# Banks_7_8.net
KiCad netlist of a schematic drawn in Altium Designer
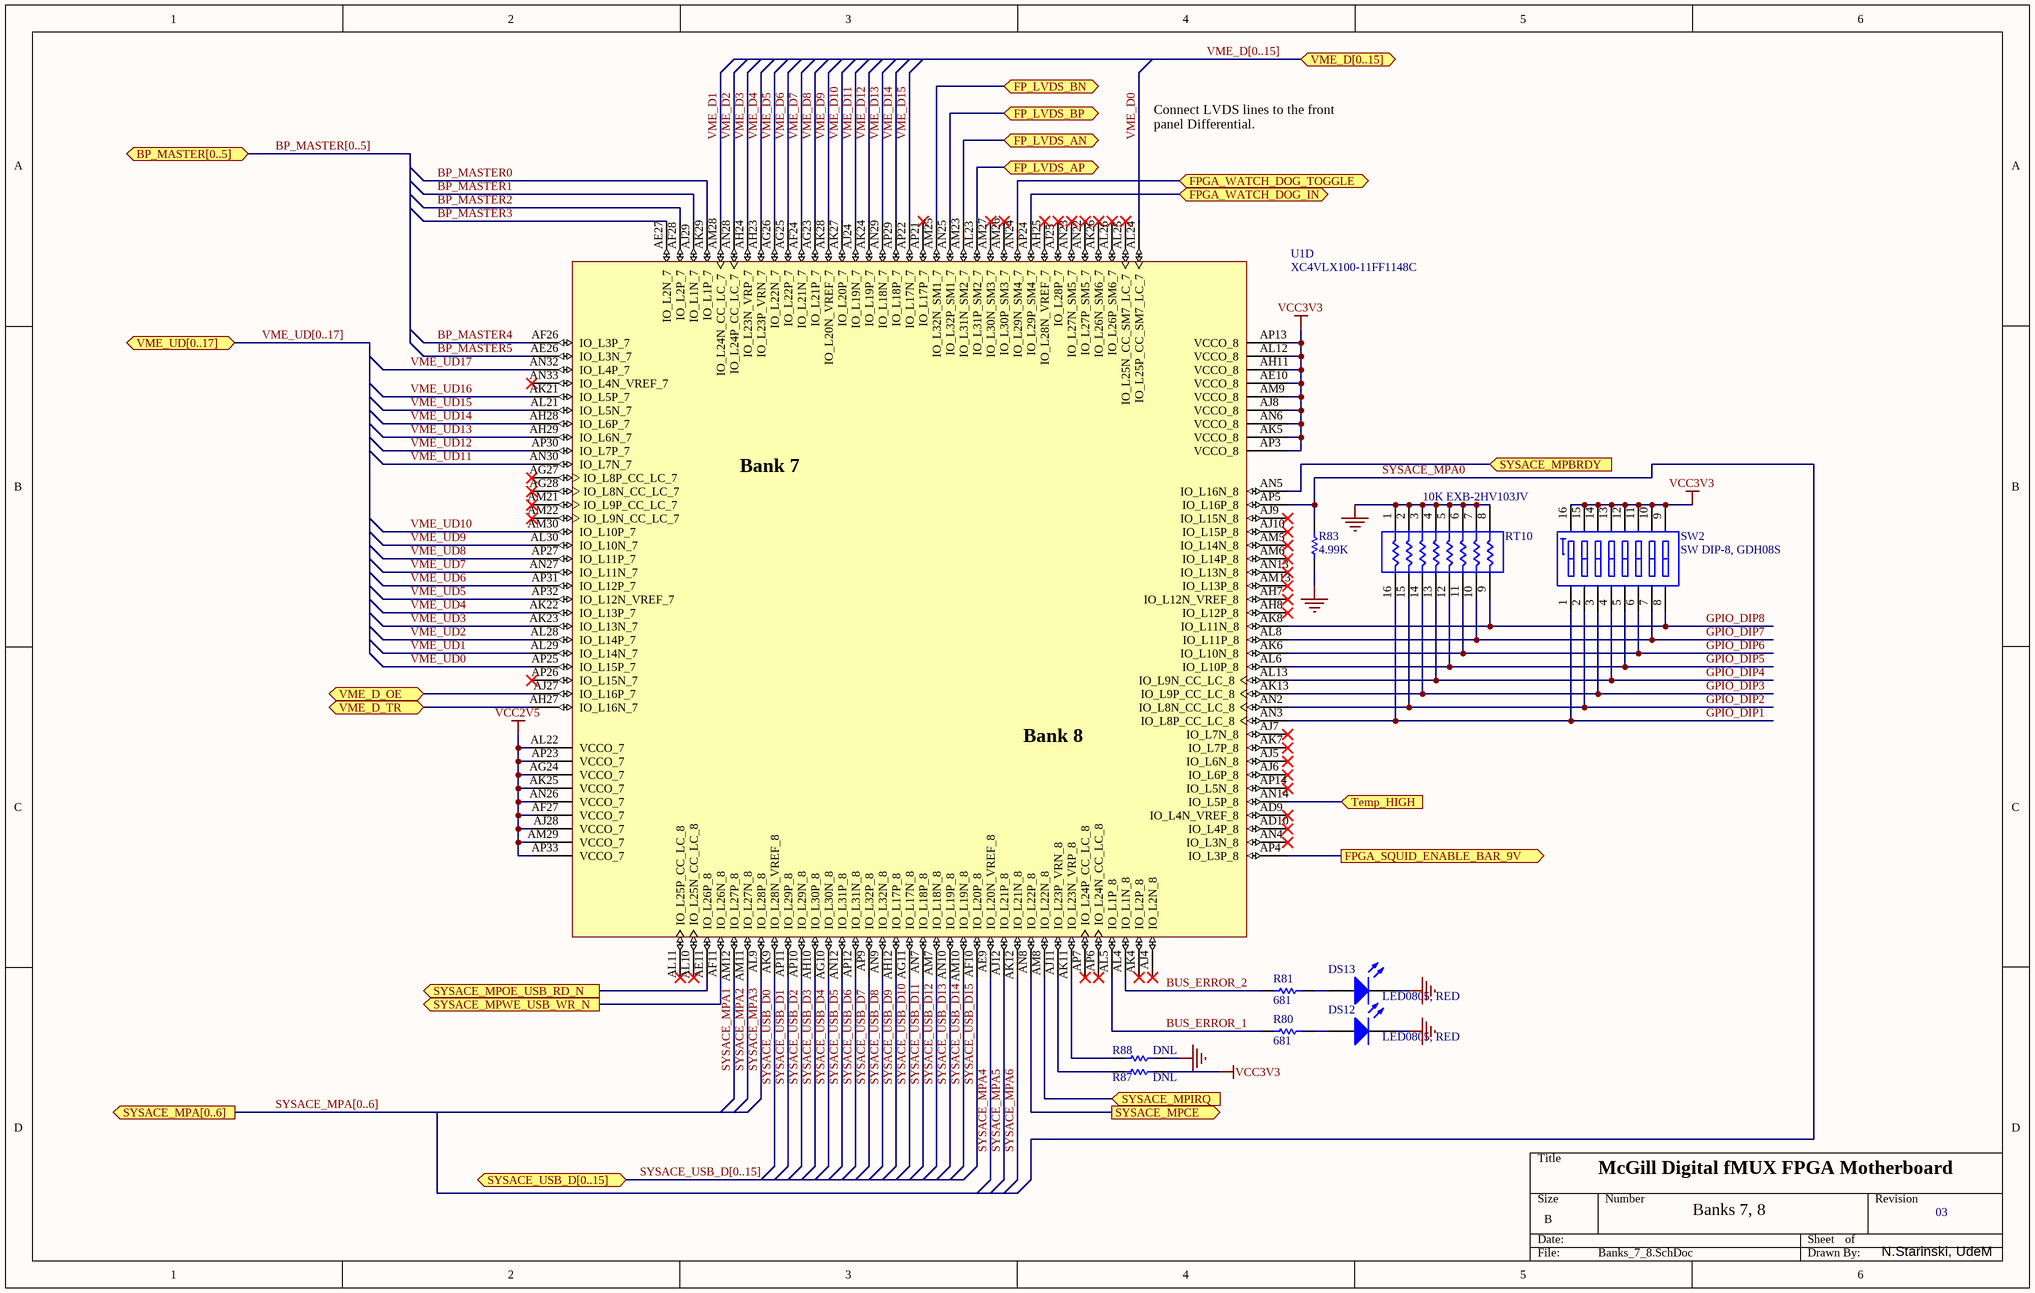
[diagram p0: Banks_7_8.SchDoc]

(export (version "E")
  (design (tool "Eeschema 10.0.6"))
  (components
    (comp (ref "DS12")
      (value "LED0805, RED")
      (footprint "SMD _LED")
      (description "LED 0805 LTST-C170CKT")
      (fields (field (name "PUBLISHER") "Altium Limited"))
      (libsource (lib "Miscellaneous Devices") (part "LED3"))
    )
    (comp (ref "DS13")
      (value "LED0805, RED")
      (footprint "SMD _LED")
      (description "LED 0805 LTST-C170CKT")
      (fields (field (name "PUBLISHER") "Altium Limited"))
      (libsource (lib "Miscellaneous Devices") (part "LED3"))
    )
    (comp (ref "R80")
      (value "681")
      (footprint "CR1608-0603")
      (description "Resistor 0603")
      (fields (field (name "PUBLISHER") "Altium Limited"))
      (libsource (lib "Miscellaneous Devices") (part "Res Semi"))
    )
    (comp (ref "R81")
      (value "681")
      (footprint "CR1608-0603")
      (description "Resistor 0603")
      (fields (field (name "PUBLISHER") "Altium Limited"))
      (libsource (lib "Miscellaneous Devices") (part "Res Semi"))
    )
    (comp (ref "R83")
      (value "4.99K")
      (footprint "CR1608-0603")
      (description "Resistor 0603")
      (fields (field (name "PUBLISHER") "Altium Limited"))
      (libsource (lib "Miscellaneous Devices") (part "Res Semi"))
    )
    (comp (ref "R87")
      (value "DNL")
      (footprint "CR1608-0603")
      (description "Semiconductor Resistor")
      (fields (field (name "PUBLISHER") "Altium Limited"))
      (libsource (lib "Miscellaneous Devices") (part "Res Semi"))
    )
    (comp (ref "R88")
      (value "DNL")
      (footprint "CR1608-0603")
      (description "Semiconductor Resistor")
      (fields (field (name "PUBLISHER") "Altium Limited"))
      (libsource (lib "Miscellaneous Devices") (part "Res Semi"))
    )
    (comp (ref "RT10")
      (value "10K EXB-2HV103JV")
      (footprint "0402_Array_2HV")
      (description "Isolated Resistor Network")
      (fields (field (name "PUBLISHER") "Altium Limited"))
      (libsource (lib "Miscellaneous Devices 02") (part "Res Pack3"))
    )
    (comp (ref "SW2")
      (value "SW DIP-8, GDH08S")
      (footprint "DIP_SW_8WAY_SMD")
      (description "DIP Switch, 8 Position, SPST")
      (fields (field (name "PUBLISHER") "Altium Limited"))
      (libsource (lib "Miscellaneous Devices 02") (part "SW DIP-8"))
    )
    (comp (ref "U1")
      (value "XC4VLX100-11FF1148C")
      (footprint "FF1148")
      (description "Xilinx Virtex-4 LX Platform FPGA, 1148-Ball FFBGA, Speed Grade 11, 768 User I/Os, Commercial Grade")
      (fields (field (name "PUBLISHER") "Altium Limited"))
      (libsource (lib "Xilinx Virtex-4") (part "XC4VLX100-11FF1148C"))
    )
  )
  (nets
    (net (code "1") (name "/BP_MASTER0") (class "Default")
      (node (ref "U1") (pin "AK29") (pinfunction "IO_L1P_7_AK29") (pintype "bidirectional"))
    )
    (net (code "2") (name "/BP_MASTER1") (class "Default")
      (node (ref "U1") (pin "AJ29") (pinfunction "IO_L1N_7_AJ29") (pintype "bidirectional"))
    )
    (net (code "3") (name "/BP_MASTER2") (class "Default")
      (node (ref "U1") (pin "AF28") (pinfunction "IO_L2P_7_AF28") (pintype "bidirectional"))
    )
    (net (code "4") (name "/BP_MASTER3") (class "Default")
      (node (ref "U1") (pin "AE27") (pinfunction "IO_L2N_7_AE27") (pintype "bidirectional"))
    )
    (net (code "5") (name "/BP_MASTER4") (class "Default")
      (node (ref "U1") (pin "AF26") (pinfunction "IO_L3P_7_AF26") (pintype "bidirectional"))
    )
    (net (code "6") (name "/BP_MASTER5") (class "Default")
      (node (ref "U1") (pin "AE26") (pinfunction "IO_L3N_7_AE26") (pintype "bidirectional"))
    )
    (net (code "8") (name "/BUS_ERROR_1") (class "Default")
      (node (ref "R80") (pin "1") (pinfunction "1_1") (pintype "passive"))
      (node (ref "U1") (pin "AL5") (pinfunction "IO_L1P_8_AL5") (pintype "bidirectional"))
    )
    (net (code "9") (name "/BUS_ERROR_2") (class "Default")
      (node (ref "R81") (pin "1") (pinfunction "1_1") (pintype "passive"))
      (node (ref "U1") (pin "AL4") (pinfunction "IO_L1N_8_AL4") (pintype "bidirectional"))
    )
    (net (code "10") (name "/FPGA_SQUID_ENABLE_BAR_9V") (class "Default")
      (node (ref "U1") (pin "AP4") (pinfunction "IO_L3P_8_AP4") (pintype "bidirectional"))
    )
    (net (code "11") (name "/FPGA_WATCH_DOG_IN") (class "Default")
      (node (ref "U1") (pin "AP24") (pinfunction "IO_L29P_SM4_7_AP24") (pintype "bidirectional"))
    )
    (net (code "12") (name "/FPGA_WATCH_DOG_TOGGLE") (class "Default")
      (node (ref "U1") (pin "AN24") (pinfunction "IO_L29N_SM4_7_AN24") (pintype "bidirectional"))
    )
    (net (code "13") (name "/FP_LVDS_AN") (class "Default")
      (node (ref "U1") (pin "AM23") (pinfunction "IO_L31N_SM2_7_AM23") (pintype "bidirectional"))
    )
    (net (code "14") (name "/FP_LVDS_AP") (class "Default")
      (node (ref "U1") (pin "AL23") (pinfunction "IO_L31P_SM2_7_AL23") (pintype "bidirectional"))
    )
    (net (code "15") (name "/FP_LVDS_BN") (class "Default")
      (node (ref "U1") (pin "AM25") (pinfunction "IO_L32N_SM1_7_AM25") (pintype "bidirectional"))
    )
    (net (code "16") (name "/FP_LVDS_BP") (class "Default")
      (node (ref "U1") (pin "AN25") (pinfunction "IO_L32P_SM1_7_AN25") (pintype "bidirectional"))
    )
    (net (code "17") (name "/GPIO_DIP1") (class "Default")
      (node (ref "RT10") (pin "16") (pinfunction "16_16") (pintype "passive"))
      (node (ref "SW2") (pin "1") (pinfunction "A1_1") (pintype "passive"))
      (node (ref "U1") (pin "AN3") (pinfunction "IO_L8P_CC_LC_8_AN3") (pintype "bidirectional"))
    )
    (net (code "18") (name "/GPIO_DIP2") (class "Default")
      (node (ref "RT10") (pin "15") (pinfunction "15_15") (pintype "passive"))
      (node (ref "SW2") (pin "2") (pinfunction "A2_2") (pintype "passive"))
      (node (ref "U1") (pin "AN2") (pinfunction "IO_L8N_CC_LC_8_AN2") (pintype "bidirectional"))
    )
    (net (code "19") (name "/GPIO_DIP3") (class "Default")
      (node (ref "RT10") (pin "14") (pinfunction "14_14") (pintype "passive"))
      (node (ref "SW2") (pin "3") (pinfunction "A3_3") (pintype "passive"))
      (node (ref "U1") (pin "AK13") (pinfunction "IO_L9P_CC_LC_8_AK13") (pintype "bidirectional"))
    )
    (net (code "20") (name "/GPIO_DIP4") (class "Default")
      (node (ref "RT10") (pin "13") (pinfunction "13_13") (pintype "passive"))
      (node (ref "SW2") (pin "4") (pinfunction "A4_4") (pintype "passive"))
      (node (ref "U1") (pin "AL13") (pinfunction "IO_L9N_CC_LC_8_AL13") (pintype "bidirectional"))
    )
    (net (code "21") (name "/GPIO_DIP5") (class "Default")
      (node (ref "RT10") (pin "12") (pinfunction "12_12") (pintype "passive"))
      (node (ref "SW2") (pin "5") (pinfunction "A5_5") (pintype "passive"))
      (node (ref "U1") (pin "AL6") (pinfunction "IO_L10P_8_AL6") (pintype "bidirectional"))
    )
    (net (code "22") (name "/GPIO_DIP6") (class "Default")
      (node (ref "RT10") (pin "11") (pinfunction "11_11") (pintype "passive"))
      (node (ref "SW2") (pin "6") (pinfunction "A6_6") (pintype "passive"))
      (node (ref "U1") (pin "AK6") (pinfunction "IO_L10N_8_AK6") (pintype "bidirectional"))
    )
    (net (code "23") (name "/GPIO_DIP7") (class "Default")
      (node (ref "RT10") (pin "10") (pinfunction "10_10") (pintype "passive"))
      (node (ref "SW2") (pin "7") (pinfunction "A7_7") (pintype "passive"))
      (node (ref "U1") (pin "AL8") (pinfunction "IO_L11P_8_AL8") (pintype "bidirectional"))
    )
    (net (code "24") (name "/GPIO_DIP8") (class "Default")
      (node (ref "RT10") (pin "9") (pinfunction "9_9") (pintype "passive"))
      (node (ref "SW2") (pin "8") (pinfunction "A8_8") (pintype "passive"))
      (node (ref "U1") (pin "AK8") (pinfunction "IO_L11N_8_AK8") (pintype "bidirectional"))
    )
    (net (code "25") (name "/SYSACE_MPA0") (class "Default")
      (node (ref "R83") (pin "2") (pinfunction "2_2") (pintype "passive"))
      (node (ref "U1") (pin "AP5") (pinfunction "IO_L16P_8_AP5") (pintype "bidirectional"))
    )
    (net (code "26") (name "/SYSACE_MPA1") (class "Default")
      (node (ref "U1") (pin "AM12") (pinfunction "IO_L27P_8_AM12") (pintype "bidirectional"))
    )
    (net (code "27") (name "/SYSACE_MPA2") (class "Default")
      (node (ref "U1") (pin "AM11") (pinfunction "IO_L27N_8_AM11") (pintype "bidirectional"))
    )
    (net (code "28") (name "/SYSACE_MPA3") (class "Default")
      (node (ref "U1") (pin "AL9") (pinfunction "IO_L28P_8_AL9") (pintype "bidirectional"))
    )
    (net (code "29") (name "/SYSACE_MPA4") (class "Default")
      (node (ref "U1") (pin "AE9") (pinfunction "IO_L20N_VREF_8_AE9") (pintype "bidirectional"))
    )
    (net (code "30") (name "/SYSACE_MPA5") (class "Default")
      (node (ref "U1") (pin "AJ12") (pinfunction "IO_L21P_8_AJ12") (pintype "bidirectional"))
    )
    (net (code "31") (name "/SYSACE_MPA6") (class "Default")
      (node (ref "U1") (pin "AK12") (pinfunction "IO_L21N_8_AK12") (pintype "bidirectional"))
    )
    (net (code "33") (name "/SYSACE_MPBRDY") (class "Default")
      (node (ref "U1") (pin "AN5") (pinfunction "IO_L16N_8_AN5") (pintype "bidirectional"))
    )
    (net (code "34") (name "/SYSACE_MPCE") (class "Default")
      (node (ref "U1") (pin "AN8") (pinfunction "IO_L22P_8_AN8") (pintype "bidirectional"))
    )
    (net (code "35") (name "/SYSACE_MPIRQ") (class "Default")
      (node (ref "U1") (pin "AM8") (pinfunction "IO_L22N_8_AM8") (pintype "bidirectional"))
    )
    (net (code "36") (name "/SYSACE_MPOE_USB_RD_N") (class "Default")
      (node (ref "U1") (pin "AE11") (pinfunction "IO_L26P_8_AE11") (pintype "bidirectional"))
    )
    (net (code "37") (name "/SYSACE_MPWE_USB_WR_N") (class "Default")
      (node (ref "U1") (pin "AF11") (pinfunction "IO_L26N_8_AF11") (pintype "bidirectional"))
    )
    (net (code "38") (name "/SYSACE_USB_D0") (class "Default")
      (node (ref "U1") (pin "AK9") (pinfunction "IO_L28N_VREF_8_AK9") (pintype "bidirectional"))
    )
    (net (code "39") (name "/SYSACE_USB_D1") (class "Default")
      (node (ref "U1") (pin "AP11") (pinfunction "IO_L29P_8_AP11") (pintype "bidirectional"))
    )
    (net (code "40") (name "/SYSACE_USB_D2") (class "Default")
      (node (ref "U1") (pin "AP10") (pinfunction "IO_L29N_8_AP10") (pintype "bidirectional"))
    )
    (net (code "41") (name "/SYSACE_USB_D3") (class "Default")
      (node (ref "U1") (pin "AH10") (pinfunction "IO_L30P_8_AH10") (pintype "bidirectional"))
    )
    (net (code "42") (name "/SYSACE_USB_D4") (class "Default")
      (node (ref "U1") (pin "AG10") (pinfunction "IO_L30N_8_AG10") (pintype "bidirectional"))
    )
    (net (code "43") (name "/SYSACE_USB_D5") (class "Default")
      (node (ref "U1") (pin "AN12") (pinfunction "IO_L31P_8_AN12") (pintype "bidirectional"))
    )
    (net (code "44") (name "/SYSACE_USB_D6") (class "Default")
      (node (ref "U1") (pin "AP12") (pinfunction "IO_L31N_8_AP12") (pintype "bidirectional"))
    )
    (net (code "45") (name "/SYSACE_USB_D7") (class "Default")
      (node (ref "U1") (pin "AP9") (pinfunction "IO_L32P_8_AP9") (pintype "bidirectional"))
    )
    (net (code "46") (name "/SYSACE_USB_D8") (class "Default")
      (node (ref "U1") (pin "AN9") (pinfunction "IO_L32N_8_AN9") (pintype "bidirectional"))
    )
    (net (code "47") (name "/SYSACE_USB_D9") (class "Default")
      (node (ref "U1") (pin "AH12") (pinfunction "IO_L17P_8_AH12") (pintype "bidirectional"))
    )
    (net (code "48") (name "/SYSACE_USB_D10") (class "Default")
      (node (ref "U1") (pin "AG11") (pinfunction "IO_L17N_8_AG11") (pintype "bidirectional"))
    )
    (net (code "49") (name "/SYSACE_USB_D11") (class "Default")
      (node (ref "U1") (pin "AN7") (pinfunction "IO_L18P_8_AN7") (pintype "bidirectional"))
    )
    (net (code "50") (name "/SYSACE_USB_D12") (class "Default")
      (node (ref "U1") (pin "AM7") (pinfunction "IO_L18N_8_AM7") (pintype "bidirectional"))
    )
    (net (code "51") (name "/SYSACE_USB_D13") (class "Default")
      (node (ref "U1") (pin "AN10") (pinfunction "IO_L19P_8_AN10") (pintype "bidirectional"))
    )
    (net (code "52") (name "/SYSACE_USB_D14") (class "Default")
      (node (ref "U1") (pin "AM10") (pinfunction "IO_L19N_8_AM10") (pintype "bidirectional"))
    )
    (net (code "53") (name "/SYSACE_USB_D15") (class "Default")
      (node (ref "U1") (pin "AF10") (pinfunction "IO_L20P_8_AF10") (pintype "bidirectional"))
    )
    (net (code "55") (name "/Temp_HIGH") (class "Default")
      (node (ref "U1") (pin "AN14") (pinfunction "IO_L5P_8_AN14") (pintype "bidirectional"))
    )
    (net (code "56") (name "/VME_D0") (class "Default")
      (node (ref "U1") (pin "AL24") (pinfunction "IO_L25P_CC_SM7_LC_7_AL24") (pintype "bidirectional"))
    )
    (net (code "57") (name "/VME_D1") (class "Default")
      (node (ref "U1") (pin "AM28") (pinfunction "IO_L24N_CC_LC_7_AM28") (pintype "bidirectional"))
    )
    (net (code "58") (name "/VME_D2") (class "Default")
      (node (ref "U1") (pin "AN28") (pinfunction "IO_L24P_CC_LC_7_AN28") (pintype "bidirectional"))
    )
    (net (code "59") (name "/VME_D3") (class "Default")
      (node (ref "U1") (pin "AH24") (pinfunction "IO_L23N_VRP_7_AH24") (pintype "bidirectional"))
    )
    (net (code "60") (name "/VME_D4") (class "Default")
      (node (ref "U1") (pin "AH23") (pinfunction "IO_L23P_VRN_7_AH23") (pintype "bidirectional"))
    )
    (net (code "61") (name "/VME_D5") (class "Default")
      (node (ref "U1") (pin "AG26") (pinfunction "IO_L22N_7_AG26") (pintype "bidirectional"))
    )
    (net (code "62") (name "/VME_D6") (class "Default")
      (node (ref "U1") (pin "AG25") (pinfunction "IO_L22P_7_AG25") (pintype "bidirectional"))
    )
    (net (code "63") (name "/VME_D7") (class "Default")
      (node (ref "U1") (pin "AF24") (pinfunction "IO_L21N_7_AF24") (pintype "bidirectional"))
    )
    (net (code "64") (name "/VME_D8") (class "Default")
      (node (ref "U1") (pin "AG23") (pinfunction "IO_L21P_7_AG23") (pintype "bidirectional"))
    )
    (net (code "65") (name "/VME_D9") (class "Default")
      (node (ref "U1") (pin "AK28") (pinfunction "IO_L20N_VREF_7_AK28") (pintype "bidirectional"))
    )
    (net (code "66") (name "/VME_D10") (class "Default")
      (node (ref "U1") (pin "AK27") (pinfunction "IO_L20P_7_AK27") (pintype "bidirectional"))
    )
    (net (code "67") (name "/VME_D11") (class "Default")
      (node (ref "U1") (pin "AJ24") (pinfunction "IO_L19N_7_AJ24") (pintype "bidirectional"))
    )
    (net (code "68") (name "/VME_D12") (class "Default")
      (node (ref "U1") (pin "AK24") (pinfunction "IO_L19P_7_AK24") (pintype "bidirectional"))
    )
    (net (code "69") (name "/VME_D13") (class "Default")
      (node (ref "U1") (pin "AN29") (pinfunction "IO_L18N_7_AN29") (pintype "bidirectional"))
    )
    (net (code "70") (name "/VME_D14") (class "Default")
      (node (ref "U1") (pin "AP29") (pinfunction "IO_L18P_7_AP29") (pintype "bidirectional"))
    )
    (net (code "71") (name "/VME_D15") (class "Default")
      (node (ref "U1") (pin "AP22") (pinfunction "IO_L17N_7_AP22") (pintype "bidirectional"))
    )
    (net (code "73") (name "/VME_D_OE") (class "Default")
      (node (ref "U1") (pin "AJ27") (pinfunction "IO_L16P_7_AJ27") (pintype "bidirectional"))
    )
    (net (code "74") (name "/VME_D_TR") (class "Default")
      (node (ref "U1") (pin "AH27") (pinfunction "IO_L16N_7_AH27") (pintype "bidirectional"))
    )
    (net (code "75") (name "/VME_UD0") (class "Default")
      (node (ref "U1") (pin "AP25") (pinfunction "IO_L15P_7_AP25") (pintype "bidirectional"))
    )
    (net (code "76") (name "/VME_UD1") (class "Default")
      (node (ref "U1") (pin "AL29") (pinfunction "IO_L14N_7_AL29") (pintype "bidirectional"))
    )
    (net (code "77") (name "/VME_UD2") (class "Default")
      (node (ref "U1") (pin "AL28") (pinfunction "IO_L14P_7_AL28") (pintype "bidirectional"))
    )
    (net (code "78") (name "/VME_UD3") (class "Default")
      (node (ref "U1") (pin "AK23") (pinfunction "IO_L13N_7_AK23") (pintype "bidirectional"))
    )
    (net (code "79") (name "/VME_UD4") (class "Default")
      (node (ref "U1") (pin "AK22") (pinfunction "IO_L13P_7_AK22") (pintype "bidirectional"))
    )
    (net (code "80") (name "/VME_UD5") (class "Default")
      (node (ref "U1") (pin "AP32") (pinfunction "IO_L12N_VREF_7_AP32") (pintype "bidirectional"))
    )
    (net (code "81") (name "/VME_UD6") (class "Default")
      (node (ref "U1") (pin "AP31") (pinfunction "IO_L12P_7_AP31") (pintype "bidirectional"))
    )
    (net (code "82") (name "/VME_UD7") (class "Default")
      (node (ref "U1") (pin "AN27") (pinfunction "IO_L11N_7_AN27") (pintype "bidirectional"))
    )
    (net (code "83") (name "/VME_UD8") (class "Default")
      (node (ref "U1") (pin "AP27") (pinfunction "IO_L11P_7_AP27") (pintype "bidirectional"))
    )
    (net (code "84") (name "/VME_UD9") (class "Default")
      (node (ref "U1") (pin "AL30") (pinfunction "IO_L10N_7_AL30") (pintype "bidirectional"))
    )
    (net (code "85") (name "/VME_UD10") (class "Default")
      (node (ref "U1") (pin "AM30") (pinfunction "IO_L10P_7_AM30") (pintype "bidirectional"))
    )
    (net (code "86") (name "/VME_UD11") (class "Default")
      (node (ref "U1") (pin "AN30") (pinfunction "IO_L7N_7_AN30") (pintype "bidirectional"))
    )
    (net (code "87") (name "/VME_UD12") (class "Default")
      (node (ref "U1") (pin "AP30") (pinfunction "IO_L7P_7_AP30") (pintype "bidirectional"))
    )
    (net (code "88") (name "/VME_UD13") (class "Default")
      (node (ref "U1") (pin "AH29") (pinfunction "IO_L6N_7_AH29") (pintype "bidirectional"))
    )
    (net (code "89") (name "/VME_UD14") (class "Default")
      (node (ref "U1") (pin "AH28") (pinfunction "IO_L6P_7_AH28") (pintype "bidirectional"))
    )
    (net (code "90") (name "/VME_UD15") (class "Default")
      (node (ref "U1") (pin "AL21") (pinfunction "IO_L5N_7_AL21") (pintype "bidirectional"))
    )
    (net (code "91") (name "/VME_UD16") (class "Default")
      (node (ref "U1") (pin "AK21") (pinfunction "IO_L5P_7_AK21") (pintype "bidirectional"))
    )
    (net (code "92") (name "/VME_UD17") (class "Default")
      (node (ref "U1") (pin "AN32") (pinfunction "IO_L4P_7_AN32") (pintype "bidirectional"))
    )
    (net (code "94") (name "GND") (class "Default")
      (node (ref "DS12") (pin "2") (pinfunction "K_2") (pintype "passive"))
      (node (ref "DS13") (pin "2") (pinfunction "K_2") (pintype "passive"))
      (node (ref "R83") (pin "1") (pinfunction "1_1") (pintype "passive"))
      (node (ref "R88") (pin "2") (pinfunction "2_2") (pintype "passive"))
      (node (ref "RT10") (pin "1") (pinfunction "1_1") (pintype "passive"))
      (node (ref "RT10") (pin "2") (pinfunction "2_2") (pintype "passive"))
      (node (ref "RT10") (pin "3") (pinfunction "3_3") (pintype "passive"))
      (node (ref "RT10") (pin "4") (pinfunction "4_4") (pintype "passive"))
      (node (ref "RT10") (pin "5") (pinfunction "5_5") (pintype "passive"))
      (node (ref "RT10") (pin "6") (pinfunction "6_6") (pintype "passive"))
      (node (ref "RT10") (pin "7") (pinfunction "7_7") (pintype "passive"))
      (node (ref "RT10") (pin "8") (pinfunction "8_8") (pintype "passive"))
    )
    (net (code "95") (name "Net-(DS12-A)") (class "Default")
      (node (ref "DS12") (pin "1") (pinfunction "A_1") (pintype "passive"))
      (node (ref "R80") (pin "2") (pinfunction "2_2") (pintype "passive"))
    )
    (net (code "96") (name "Net-(DS13-A)") (class "Default")
      (node (ref "DS13") (pin "1") (pinfunction "A_1") (pintype "passive"))
      (node (ref "R81") (pin "2") (pinfunction "2_2") (pintype "passive"))
    )
    (net (code "97") (name "Net-(U1D-IO_L23N_VRP_8)") (class "Default")
      (node (ref "R88") (pin "1") (pinfunction "1_1") (pintype "passive"))
      (node (ref "U1") (pin "AK11") (pinfunction "IO_L23N_VRP_8_AK11") (pintype "bidirectional"))
    )
    (net (code "98") (name "Net-(U1D-IO_L23P_VRN_8)") (class "Default")
      (node (ref "R87") (pin "1") (pinfunction "1_1") (pintype "passive"))
      (node (ref "U1") (pin "AJ11") (pinfunction "IO_L23P_VRN_8_AJ11") (pintype "bidirectional"))
    )
    (net (code "99") (name "VCC2V5") (class "Default")
      (node (ref "U1") (pin "AF27") (pinfunction "VCCO_7_AF27") (pintype "power_in"))
      (node (ref "U1") (pin "AG24") (pinfunction "VCCO_7_AG24") (pintype "power_in"))
      (node (ref "U1") (pin "AJ28") (pinfunction "VCCO_7_AJ28") (pintype "power_in"))
      (node (ref "U1") (pin "AK25") (pinfunction "VCCO_7_AK25") (pintype "power_in"))
      (node (ref "U1") (pin "AL22") (pinfunction "VCCO_7_AL22") (pintype "power_in"))
      (node (ref "U1") (pin "AM29") (pinfunction "VCCO_7_AM29") (pintype "power_in"))
      (node (ref "U1") (pin "AN26") (pinfunction "VCCO_7_AN26") (pintype "power_in"))
      (node (ref "U1") (pin "AP23") (pinfunction "VCCO_7_AP23") (pintype "power_in"))
      (node (ref "U1") (pin "AP33") (pinfunction "VCCO_7_AP33") (pintype "power_in"))
    )
    (net (code "100") (name "VCC3V3") (class "Default")
      (node (ref "R87") (pin "2") (pinfunction "2_2") (pintype "passive"))
      (node (ref "SW2") (pin "10") (pinfunction "B7_10") (pintype "passive"))
      (node (ref "SW2") (pin "11") (pinfunction "B6_11") (pintype "passive"))
      (node (ref "SW2") (pin "12") (pinfunction "B5_12") (pintype "passive"))
      (node (ref "SW2") (pin "13") (pinfunction "B4_13") (pintype "passive"))
      (node (ref "SW2") (pin "14") (pinfunction "B3_14") (pintype "passive"))
      (node (ref "SW2") (pin "15") (pinfunction "B2_15") (pintype "passive"))
      (node (ref "SW2") (pin "16") (pinfunction "B1_16") (pintype "passive"))
      (node (ref "SW2") (pin "9") (pinfunction "B8_9") (pintype "passive"))
      (node (ref "U1") (pin "AE10") (pinfunction "VCCO_8_AE10") (pintype "power_in"))
      (node (ref "U1") (pin "AH11") (pinfunction "VCCO_8_AH11") (pintype "power_in"))
      (node (ref "U1") (pin "AJ8") (pinfunction "VCCO_8_AJ8") (pintype "power_in"))
      (node (ref "U1") (pin "AK5") (pinfunction "VCCO_8_AK5") (pintype "power_in"))
      (node (ref "U1") (pin "AL12") (pinfunction "VCCO_8_AL12") (pintype "power_in"))
      (node (ref "U1") (pin "AM9") (pinfunction "VCCO_8_AM9") (pintype "power_in"))
      (node (ref "U1") (pin "AN6") (pinfunction "VCCO_8_AN6") (pintype "power_in"))
      (node (ref "U1") (pin "AP13") (pinfunction "VCCO_8_AP13") (pintype "power_in"))
      (node (ref "U1") (pin "AP3") (pinfunction "VCCO_8_AP3") (pintype "power_in"))
    )
    (net (code "101") (name "unconnected-(U1D-IO_L2N_8-PadAJ4)") (class "Default")
      (node (ref "U1") (pin "AJ4") (pinfunction "IO_L2N_8_AJ4") (pintype "bidirectional+no_connect"))
    )
    (net (code "102") (name "unconnected-(U1D-IO_L2P_8-PadAK4)") (class "Default")
      (node (ref "U1") (pin "AK4") (pinfunction "IO_L2P_8_AK4") (pintype "bidirectional+no_connect"))
    )
    (net (code "103") (name "unconnected-(U1D-IO_L3N_8-PadAN4)") (class "Default")
      (node (ref "U1") (pin "AN4") (pinfunction "IO_L3N_8_AN4") (pintype "bidirectional+no_connect"))
    )
    (net (code "104") (name "unconnected-(U1D-IO_L4N_VREF_7-PadAN33)") (class "Default")
      (node (ref "U1") (pin "AN33") (pinfunction "IO_L4N_VREF_7_AN33") (pintype "bidirectional+no_connect"))
    )
    (net (code "105") (name "unconnected-(U1D-IO_L4N_VREF_8-PadAD9)") (class "Default")
      (node (ref "U1") (pin "AD9") (pinfunction "IO_L4N_VREF_8_AD9") (pintype "bidirectional+no_connect"))
    )
    (net (code "106") (name "unconnected-(U1D-IO_L4P_8-PadAD10)") (class "Default")
      (node (ref "U1") (pin "AD10") (pinfunction "IO_L4P_8_AD10") (pintype "bidirectional+no_connect"))
    )
    (net (code "107") (name "unconnected-(U1D-IO_L5N_8-PadAP14)") (class "Default")
      (node (ref "U1") (pin "AP14") (pinfunction "IO_L5N_8_AP14") (pintype "bidirectional+no_connect"))
    )
    (net (code "108") (name "unconnected-(U1D-IO_L6N_8-PadAJ5)") (class "Default")
      (node (ref "U1") (pin "AJ5") (pinfunction "IO_L6N_8_AJ5") (pintype "bidirectional+no_connect"))
    )
    (net (code "109") (name "unconnected-(U1D-IO_L6P_8-PadAJ6)") (class "Default")
      (node (ref "U1") (pin "AJ6") (pinfunction "IO_L6P_8_AJ6") (pintype "bidirectional+no_connect"))
    )
    (net (code "110") (name "unconnected-(U1D-IO_L7N_8-PadAJ7)") (class "Default")
      (node (ref "U1") (pin "AJ7") (pinfunction "IO_L7N_8_AJ7") (pintype "bidirectional+no_connect"))
    )
    (net (code "111") (name "unconnected-(U1D-IO_L7P_8-PadAK7)") (class "Default")
      (node (ref "U1") (pin "AK7") (pinfunction "IO_L7P_8_AK7") (pintype "bidirectional+no_connect"))
    )
    (net (code "112") (name "unconnected-(U1D-IO_L8N_CC_LC_7-PadAG28)") (class "Default")
      (node (ref "U1") (pin "AG28") (pinfunction "IO_L8N_CC_LC_7_AG28") (pintype "bidirectional+no_connect"))
    )
    (net (code "113") (name "unconnected-(U1D-IO_L8P_CC_LC_7-PadAG27)") (class "Default")
      (node (ref "U1") (pin "AG27") (pinfunction "IO_L8P_CC_LC_7_AG27") (pintype "bidirectional+no_connect"))
    )
    (net (code "114") (name "unconnected-(U1D-IO_L9N_CC_LC_7-PadAM22)") (class "Default")
      (node (ref "U1") (pin "AM22") (pinfunction "IO_L9N_CC_LC_7_AM22") (pintype "bidirectional+no_connect"))
    )
    (net (code "115") (name "unconnected-(U1D-IO_L9P_CC_LC_7-PadAM21)") (class "Default")
      (node (ref "U1") (pin "AM21") (pinfunction "IO_L9P_CC_LC_7_AM21") (pintype "bidirectional+no_connect"))
    )
    (net (code "116") (name "unconnected-(U1D-IO_L12N_VREF_8-PadAH7)") (class "Default")
      (node (ref "U1") (pin "AH7") (pinfunction "IO_L12N_VREF_8_AH7") (pintype "bidirectional+no_connect"))
    )
    (net (code "117") (name "unconnected-(U1D-IO_L12P_8-PadAH8)") (class "Default")
      (node (ref "U1") (pin "AH8") (pinfunction "IO_L12P_8_AH8") (pintype "bidirectional+no_connect"))
    )
    (net (code "118") (name "unconnected-(U1D-IO_L13N_8-PadAN13)") (class "Default")
      (node (ref "U1") (pin "AN13") (pinfunction "IO_L13N_8_AN13") (pintype "bidirectional+no_connect"))
    )
    (net (code "119") (name "unconnected-(U1D-IO_L13P_8-PadAM13)") (class "Default")
      (node (ref "U1") (pin "AM13") (pinfunction "IO_L13P_8_AM13") (pintype "bidirectional+no_connect"))
    )
    (net (code "120") (name "unconnected-(U1D-IO_L14N_8-PadAM5)") (class "Default")
      (node (ref "U1") (pin "AM5") (pinfunction "IO_L14N_8_AM5") (pintype "bidirectional+no_connect"))
    )
    (net (code "121") (name "unconnected-(U1D-IO_L14P_8-PadAM6)") (class "Default")
      (node (ref "U1") (pin "AM6") (pinfunction "IO_L14P_8_AM6") (pintype "bidirectional+no_connect"))
    )
    (net (code "122") (name "unconnected-(U1D-IO_L15N_7-PadAP26)") (class "Default")
      (node (ref "U1") (pin "AP26") (pinfunction "IO_L15N_7_AP26") (pintype "bidirectional+no_connect"))
    )
    (net (code "123") (name "unconnected-(U1D-IO_L15N_8-PadAJ9)") (class "Default")
      (node (ref "U1") (pin "AJ9") (pinfunction "IO_L15N_8_AJ9") (pintype "bidirectional+no_connect"))
    )
    (net (code "124") (name "unconnected-(U1D-IO_L15P_8-PadAJ10)") (class "Default")
      (node (ref "U1") (pin "AJ10") (pinfunction "IO_L15P_8_AJ10") (pintype "bidirectional+no_connect"))
    )
    (net (code "125") (name "unconnected-(U1D-IO_L17P_7-PadAP21)") (class "Default")
      (node (ref "U1") (pin "AP21") (pinfunction "IO_L17P_7_AP21") (pintype "bidirectional+no_connect"))
    )
    (net (code "126") (name "unconnected-(U1D-IO_L24N_CC_LC_8-PadAP6)") (class "Default")
      (node (ref "U1") (pin "AP6") (pinfunction "IO_L24N_CC_LC_8_AP6") (pintype "bidirectional+no_connect"))
    )
    (net (code "127") (name "unconnected-(U1D-IO_L24P_CC_LC_8-PadAP7)") (class "Default")
      (node (ref "U1") (pin "AP7") (pinfunction "IO_L24P_CC_LC_8_AP7") (pintype "bidirectional+no_connect"))
    )
    (net (code "128") (name "unconnected-(U1D-IO_L25N_CC_LC_8-PadAL10)") (class "Default")
      (node (ref "U1") (pin "AL10") (pinfunction "IO_L25N_CC_LC_8_AL10") (pintype "bidirectional+no_connect"))
    )
    (net (code "129") (name "unconnected-(U1D-IO_L25N_CC_SM7_LC_7-PadAL25)") (class "Default")
      (node (ref "U1") (pin "AL25") (pinfunction "IO_L25N_CC_SM7_LC_7_AL25") (pintype "bidirectional+no_connect"))
    )
    (net (code "130") (name "unconnected-(U1D-IO_L25P_CC_LC_8-PadAL11)") (class "Default")
      (node (ref "U1") (pin "AL11") (pinfunction "IO_L25P_CC_LC_8_AL11") (pintype "bidirectional+no_connect"))
    )
    (net (code "131") (name "unconnected-(U1D-IO_L26N_SM6_7-PadAK26)") (class "Default")
      (node (ref "U1") (pin "AK26") (pinfunction "IO_L26N_SM6_7_AK26") (pintype "bidirectional+no_connect"))
    )
    (net (code "132") (name "unconnected-(U1D-IO_L26P_SM6_7-PadAL26)") (class "Default")
      (node (ref "U1") (pin "AL26") (pinfunction "IO_L26P_SM6_7_AL26") (pintype "bidirectional+no_connect"))
    )
    (net (code "133") (name "unconnected-(U1D-IO_L27N_SM5_7-PadAN23)") (class "Default")
      (node (ref "U1") (pin "AN23") (pinfunction "IO_L27N_SM5_7_AN23") (pintype "bidirectional+no_connect"))
    )
    (net (code "134") (name "unconnected-(U1D-IO_L27P_SM5_7-PadAN22)") (class "Default")
      (node (ref "U1") (pin "AN22") (pinfunction "IO_L27P_SM5_7_AN22") (pintype "bidirectional+no_connect"))
    )
    (net (code "135") (name "unconnected-(U1D-IO_L28N_VREF_7-PadAH25)") (class "Default")
      (node (ref "U1") (pin "AH25") (pinfunction "IO_L28N_VREF_7_AH25") (pintype "bidirectional+no_connect"))
    )
    (net (code "136") (name "unconnected-(U1D-IO_L28P_7-PadAJ25)") (class "Default")
      (node (ref "U1") (pin "AJ25") (pinfunction "IO_L28P_7_AJ25") (pintype "bidirectional+no_connect"))
    )
    (net (code "137") (name "unconnected-(U1D-IO_L30N_SM3_7-PadAM27)") (class "Default")
      (node (ref "U1") (pin "AM27") (pinfunction "IO_L30N_SM3_7_AM27") (pintype "bidirectional+no_connect"))
    )
    (net (code "138") (name "unconnected-(U1D-IO_L30P_SM3_7-PadAM26)") (class "Default")
      (node (ref "U1") (pin "AM26") (pinfunction "IO_L30P_SM3_7_AM26") (pintype "bidirectional+no_connect"))
    )
  )
)
